# servo_driver_and_imu_device.net
KiCad netlist of a schematic drawn in Altium Designer
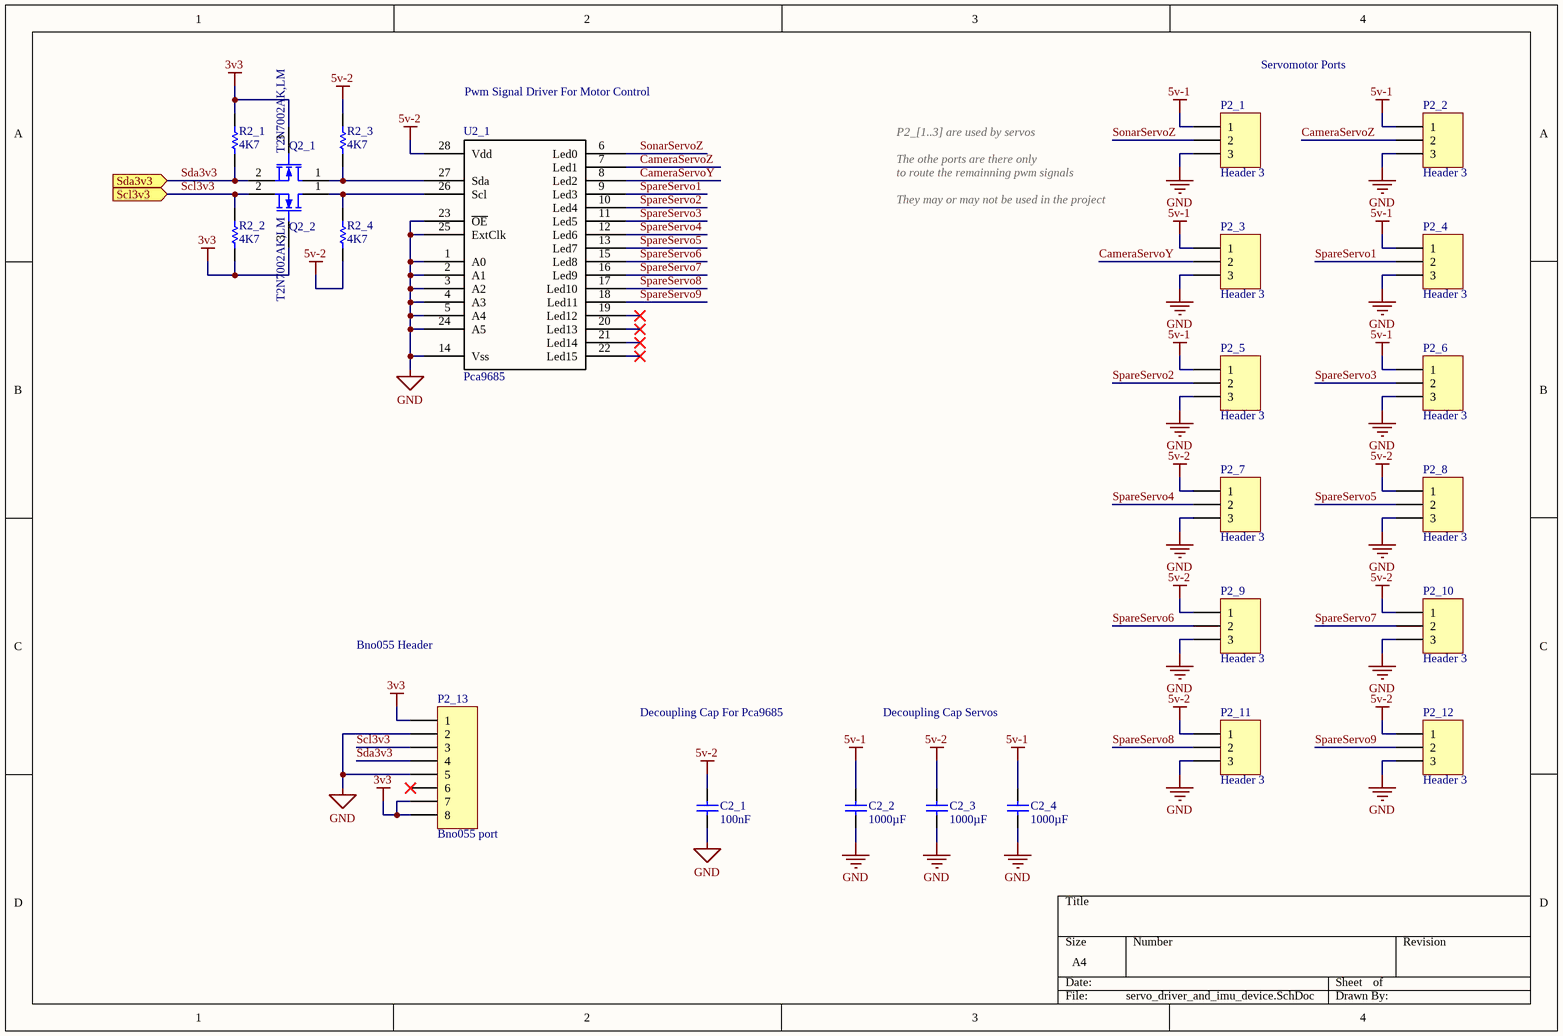
[diagram p0: servo_driver_and_imu_device.SchDoc]

(export (version "E")
  (design (tool "Eeschema 10.0.6"))
  (components
    (comp (ref "C2_1")
      (value "100nF")
      (footprint "C1206")
      (description "Capacitor")
      (fields (field (name "Comment") "12063C104MAT2A") (field (name "PUBLISHER") "Altium Limited"))
      (libsource (lib "Miscellaneous Devices") (part "Cap"))
    )
    (comp (ref "C2_2")
      (value "1000µF")
      (footprint "CAP-ELECTRO-KE0")
      (description "Capacitor")
      (fields (field (name "Comment") "EMHS250GRA102MKE0S") (field (name "PUBLISHER") "Altium Limited"))
      (libsource (lib "Miscellaneous Devices") (part "Cap"))
    )
    (comp (ref "C2_3")
      (value "1000µF")
      (footprint "CAP-ELECTRO-KE0")
      (description "Capacitor")
      (fields (field (name "Comment") "EMHS250GRA102MKE0S") (field (name "PUBLISHER") "Altium Limited"))
      (libsource (lib "Miscellaneous Devices") (part "Cap"))
    )
    (comp (ref "C2_4")
      (value "1000µF")
      (footprint "CAP-ELECTRO-KE0")
      (description "Capacitor")
      (fields (field (name "Comment") "EMHS250GRA102MKE0S") (field (name "PUBLISHER") "Altium Limited"))
      (libsource (lib "Miscellaneous Devices") (part "Cap"))
    )
    (comp (ref "P2_1")
      (value "Header 3")
      (footprint "HDR1X3-42")
      (description "Header, 3-Pin")
      (fields (field (name "PUBLISHER") "Altium Limited"))
      (libsource (lib "Miscellaneous Connectors") (part "Header 3"))
    )
    (comp (ref "P2_2")
      (value "Header 3")
      (footprint "HDR1X3-42")
      (description "Header, 3-Pin")
      (fields (field (name "PUBLISHER") "Altium Limited"))
      (libsource (lib "Miscellaneous Connectors") (part "Header 3"))
    )
    (comp (ref "P2_3")
      (value "Header 3")
      (footprint "HDR1X3-42")
      (description "Header, 3-Pin")
      (fields (field (name "PUBLISHER") "Altium Limited"))
      (libsource (lib "Miscellaneous Connectors") (part "Header 3"))
    )
    (comp (ref "P2_4")
      (value "Header 3")
      (footprint "HDR1X3-42")
      (description "Header, 3-Pin")
      (fields (field (name "PUBLISHER") "Altium Limited"))
      (libsource (lib "Miscellaneous Connectors") (part "Header 3"))
    )
    (comp (ref "P2_5")
      (value "Header 3")
      (footprint "HDR1X3-42")
      (description "Header, 3-Pin")
      (fields (field (name "PUBLISHER") "Altium Limited"))
      (libsource (lib "Miscellaneous Connectors") (part "Header 3"))
    )
    (comp (ref "P2_6")
      (value "Header 3")
      (footprint "HDR1X3-42")
      (description "Header, 3-Pin")
      (fields (field (name "PUBLISHER") "Altium Limited"))
      (libsource (lib "Miscellaneous Connectors") (part "Header 3"))
    )
    (comp (ref "P2_7")
      (value "Header 3")
      (footprint "HDR1X3-42")
      (description "Header, 3-Pin")
      (fields (field (name "PUBLISHER") "Altium Limited"))
      (libsource (lib "Miscellaneous Connectors") (part "Header 3"))
    )
    (comp (ref "P2_8")
      (value "Header 3")
      (footprint "HDR1X3-42")
      (description "Header, 3-Pin")
      (fields (field (name "PUBLISHER") "Altium Limited"))
      (libsource (lib "Miscellaneous Connectors") (part "Header 3"))
    )
    (comp (ref "P2_9")
      (value "Header 3")
      (footprint "HDR1X3-42")
      (description "Header, 3-Pin")
      (fields (field (name "PUBLISHER") "Altium Limited"))
      (libsource (lib "Miscellaneous Connectors") (part "Header 3"))
    )
    (comp (ref "P2_10")
      (value "Header 3")
      (footprint "HDR1X3-42")
      (description "Header, 3-Pin")
      (fields (field (name "PUBLISHER") "Altium Limited"))
      (libsource (lib "Miscellaneous Connectors") (part "Header 3"))
    )
    (comp (ref "P2_11")
      (value "Header 3")
      (footprint "HDR1X3-42")
      (description "Header, 3-Pin")
      (fields (field (name "PUBLISHER") "Altium Limited"))
      (libsource (lib "Miscellaneous Connectors") (part "Header 3"))
    )
    (comp (ref "P2_12")
      (value "Header 3")
      (footprint "HDR1X3-42")
      (description "Header, 3-Pin")
      (fields (field (name "PUBLISHER") "Altium Limited"))
      (libsource (lib "Miscellaneous Connectors") (part "Header 3"))
    )
    (comp (ref "P2_13")
      (value "Bno055 port")
      (footprint "HDR1X8-42")
      (description "Header, 8-Pin")
      (fields (field (name "PUBLISHER") "Altium Limited"))
      (libsource (lib "Miscellaneous Connectors") (part "Header 8"))
    )
    (comp (ref "Q2_1")
      (value "T2N7002AK,LM")
      (footprint "SOT23_L")
      (description "N-Channel MOSFET")
      (fields (field (name "PUBLISHER") "Altium Limited"))
      (libsource (lib "Miscellaneous Devices") (part "MOSFET-N"))
    )
    (comp (ref "Q2_2")
      (value "T2N7002AK,LM")
      (footprint "SOT23_L")
      (description "N-Channel MOSFET")
      (fields (field (name "PUBLISHER") "Altium Limited"))
      (libsource (lib "Miscellaneous Devices") (part "MOSFET-N"))
    )
    (comp (ref "R2_1")
      (value "4K7")
      (footprint "C1206")
      (description "Resistor")
      (fields (field (name "Comment") "Res1") (field (name "PUBLISHER") "Altium Limited"))
      (libsource (lib "Miscellaneous Devices") (part "Res1"))
    )
    (comp (ref "R2_2")
      (value "4K7")
      (footprint "C1206")
      (description "Resistor")
      (fields (field (name "Comment") "Res1") (field (name "PUBLISHER") "Altium Limited"))
      (libsource (lib "Miscellaneous Devices") (part "Res1"))
    )
    (comp (ref "R2_3")
      (value "4K7")
      (footprint "C1206")
      (description "Resistor")
      (fields (field (name "Comment") "Res1") (field (name "PUBLISHER") "Altium Limited"))
      (libsource (lib "Miscellaneous Devices") (part "Res1"))
    )
    (comp (ref "R2_4")
      (value "4K7")
      (footprint "C1206")
      (description "Resistor")
      (fields (field (name "Comment") "Res1") (field (name "PUBLISHER") "Altium Limited"))
      (libsource (lib "Miscellaneous Devices") (part "Res1"))
    )
    (comp (ref "U2_1")
      (value "Pca9685")
      (footprint "SOP65P640X110-28N")
      (description "Serial pwm led driver")
      (libsource (lib "projet 6e session") (part "Pca9685"))
    )
  )
  (nets
    (net (code "1") (name "/CameraServoY") (class "Default")
      (node (ref "P2_3") (pin "2") (pinfunction "2_2") (pintype "passive"))
      (node (ref "U2_1") (pin "8") (pinfunction "Led2_8") (pintype "passive"))
    )
    (net (code "2") (name "/CameraServoZ") (class "Default")
      (node (ref "P2_2") (pin "2") (pinfunction "2_2") (pintype "passive"))
      (node (ref "U2_1") (pin "7") (pinfunction "Led1_7") (pintype "passive"))
    )
    (net (code "3") (name "/Scl3v3") (class "Default")
      (node (ref "P2_13") (pin "3") (pinfunction "3_3") (pintype "passive"))
      (node (ref "Q2_2") (pin "2") (pinfunction "S_2") (pintype "passive"))
      (node (ref "R2_2") (pin "1") (pinfunction "1_1") (pintype "passive"))
    )
    (net (code "4") (name "/Sda3v3") (class "Default")
      (node (ref "P2_13") (pin "4") (pinfunction "4_4") (pintype "passive"))
      (node (ref "Q2_1") (pin "2") (pinfunction "S_2") (pintype "passive"))
      (node (ref "R2_1") (pin "2") (pinfunction "2_2") (pintype "passive"))
    )
    (net (code "5") (name "/SonarServoZ") (class "Default")
      (node (ref "P2_1") (pin "2") (pinfunction "2_2") (pintype "passive"))
      (node (ref "U2_1") (pin "6") (pinfunction "Led0_6") (pintype "passive"))
    )
    (net (code "6") (name "/SpareServo1") (class "Default")
      (node (ref "P2_4") (pin "2") (pinfunction "2_2") (pintype "passive"))
      (node (ref "U2_1") (pin "9") (pinfunction "Led3_9") (pintype "passive"))
    )
    (net (code "7") (name "/SpareServo2") (class "Default")
      (node (ref "P2_5") (pin "2") (pinfunction "2_2") (pintype "passive"))
      (node (ref "U2_1") (pin "10") (pinfunction "Led4_10") (pintype "passive"))
    )
    (net (code "8") (name "/SpareServo3") (class "Default")
      (node (ref "P2_6") (pin "2") (pinfunction "2_2") (pintype "passive"))
      (node (ref "U2_1") (pin "11") (pinfunction "Led5_11") (pintype "passive"))
    )
    (net (code "9") (name "/SpareServo4") (class "Default")
      (node (ref "P2_7") (pin "2") (pinfunction "2_2") (pintype "passive"))
      (node (ref "U2_1") (pin "12") (pinfunction "Led6_12") (pintype "passive"))
    )
    (net (code "10") (name "/SpareServo5") (class "Default")
      (node (ref "P2_8") (pin "2") (pinfunction "2_2") (pintype "passive"))
      (node (ref "U2_1") (pin "13") (pinfunction "Led7_13") (pintype "passive"))
    )
    (net (code "11") (name "/SpareServo6") (class "Default")
      (node (ref "P2_9") (pin "2") (pinfunction "2_2") (pintype "passive"))
      (node (ref "U2_1") (pin "15") (pinfunction "Led8_15") (pintype "passive"))
    )
    (net (code "12") (name "/SpareServo7") (class "Default")
      (node (ref "P2_10") (pin "2") (pinfunction "2_2") (pintype "passive"))
      (node (ref "U2_1") (pin "16") (pinfunction "Led9_16") (pintype "passive"))
    )
    (net (code "13") (name "/SpareServo8") (class "Default")
      (node (ref "P2_11") (pin "2") (pinfunction "2_2") (pintype "passive"))
      (node (ref "U2_1") (pin "17") (pinfunction "Led10_17") (pintype "passive"))
    )
    (net (code "14") (name "/SpareServo9") (class "Default")
      (node (ref "P2_12") (pin "2") (pinfunction "2_2") (pintype "passive"))
      (node (ref "U2_1") (pin "18") (pinfunction "Led11_18") (pintype "passive"))
    )
    (net (code "15") (name "3v3") (class "Default")
      (node (ref "P2_13") (pin "1") (pinfunction "1_1") (pintype "passive"))
      (node (ref "P2_13") (pin "7") (pinfunction "7_7") (pintype "passive"))
      (node (ref "P2_13") (pin "8") (pinfunction "8_8") (pintype "passive"))
      (node (ref "Q2_1") (pin "3") (pinfunction "G_3") (pintype "passive"))
      (node (ref "Q2_2") (pin "3") (pinfunction "G_3") (pintype "passive"))
      (node (ref "R2_1") (pin "1") (pinfunction "1_1") (pintype "passive"))
      (node (ref "R2_2") (pin "2") (pinfunction "2_2") (pintype "passive"))
    )
    (net (code "16") (name "5v-1") (class "Default")
      (node (ref "C2_2") (pin "1") (pinfunction "1_1") (pintype "passive"))
      (node (ref "C2_4") (pin "1") (pinfunction "1_1") (pintype "passive"))
      (node (ref "P2_1") (pin "1") (pinfunction "1_1") (pintype "passive"))
      (node (ref "P2_2") (pin "1") (pinfunction "1_1") (pintype "passive"))
      (node (ref "P2_3") (pin "1") (pinfunction "1_1") (pintype "passive"))
      (node (ref "P2_4") (pin "1") (pinfunction "1_1") (pintype "passive"))
      (node (ref "P2_5") (pin "1") (pinfunction "1_1") (pintype "passive"))
      (node (ref "P2_6") (pin "1") (pinfunction "1_1") (pintype "passive"))
    )
    (net (code "17") (name "5v-2") (class "Default")
      (node (ref "C2_1") (pin "1") (pinfunction "1_1") (pintype "passive"))
      (node (ref "C2_3") (pin "1") (pinfunction "1_1") (pintype "passive"))
      (node (ref "P2_10") (pin "1") (pinfunction "1_1") (pintype "passive"))
      (node (ref "P2_11") (pin "1") (pinfunction "1_1") (pintype "passive"))
      (node (ref "P2_12") (pin "1") (pinfunction "1_1") (pintype "passive"))
      (node (ref "P2_7") (pin "1") (pinfunction "1_1") (pintype "passive"))
      (node (ref "P2_8") (pin "1") (pinfunction "1_1") (pintype "passive"))
      (node (ref "P2_9") (pin "1") (pinfunction "1_1") (pintype "passive"))
      (node (ref "R2_3") (pin "1") (pinfunction "1_1") (pintype "passive"))
      (node (ref "R2_4") (pin "2") (pinfunction "2_2") (pintype "passive"))
      (node (ref "U2_1") (pin "28") (pinfunction "Vdd_28") (pintype "passive"))
    )
    (net (code "18") (name "GND") (class "Default")
      (node (ref "C2_1") (pin "2") (pinfunction "2_2") (pintype "passive"))
      (node (ref "C2_2") (pin "2") (pinfunction "2_2") (pintype "passive"))
      (node (ref "C2_3") (pin "2") (pinfunction "2_2") (pintype "passive"))
      (node (ref "C2_4") (pin "2") (pinfunction "2_2") (pintype "passive"))
      (node (ref "P2_1") (pin "3") (pinfunction "3_3") (pintype "passive"))
      (node (ref "P2_10") (pin "3") (pinfunction "3_3") (pintype "passive"))
      (node (ref "P2_11") (pin "3") (pinfunction "3_3") (pintype "passive"))
      (node (ref "P2_12") (pin "3") (pinfunction "3_3") (pintype "passive"))
      (node (ref "P2_13") (pin "2") (pinfunction "2_2") (pintype "passive"))
      (node (ref "P2_13") (pin "5") (pinfunction "5_5") (pintype "passive"))
      (node (ref "P2_2") (pin "3") (pinfunction "3_3") (pintype "passive"))
      (node (ref "P2_3") (pin "3") (pinfunction "3_3") (pintype "passive"))
      (node (ref "P2_4") (pin "3") (pinfunction "3_3") (pintype "passive"))
      (node (ref "P2_5") (pin "3") (pinfunction "3_3") (pintype "passive"))
      (node (ref "P2_6") (pin "3") (pinfunction "3_3") (pintype "passive"))
      (node (ref "P2_7") (pin "3") (pinfunction "3_3") (pintype "passive"))
      (node (ref "P2_8") (pin "3") (pinfunction "3_3") (pintype "passive"))
      (node (ref "P2_9") (pin "3") (pinfunction "3_3") (pintype "passive"))
      (node (ref "U2_1") (pin "1") (pinfunction "A0_1") (pintype "passive"))
      (node (ref "U2_1") (pin "14") (pinfunction "Vss_14") (pintype "passive"))
      (node (ref "U2_1") (pin "2") (pinfunction "A1_2") (pintype "passive"))
      (node (ref "U2_1") (pin "23") (pinfunction "~{OE}_23") (pintype "passive"))
      (node (ref "U2_1") (pin "24") (pinfunction "A5_24") (pintype "passive"))
      (node (ref "U2_1") (pin "25") (pinfunction "ExtClk_25") (pintype "passive"))
      (node (ref "U2_1") (pin "3") (pinfunction "A2_3") (pintype "passive"))
      (node (ref "U2_1") (pin "4") (pinfunction "A3_4") (pintype "passive"))
      (node (ref "U2_1") (pin "5") (pinfunction "A4_5") (pintype "passive"))
    )
    (net (code "19") (name "Net-(Q2_1-D)") (class "Default")
      (node (ref "Q2_1") (pin "1") (pinfunction "D_1") (pintype "passive"))
      (node (ref "R2_3") (pin "2") (pinfunction "2_2") (pintype "passive"))
      (node (ref "U2_1") (pin "27") (pinfunction "Sda_27") (pintype "passive"))
    )
    (net (code "20") (name "Net-(Q2_2-D)") (class "Default")
      (node (ref "Q2_2") (pin "1") (pinfunction "D_1") (pintype "passive"))
      (node (ref "R2_4") (pin "1") (pinfunction "1_1") (pintype "passive"))
      (node (ref "U2_1") (pin "26") (pinfunction "Scl_26") (pintype "passive"))
    )
    (net (code "21") (name "unconnected-(P2_13-Pad6)") (class "Default")
      (node (ref "P2_13") (pin "6") (pinfunction "6_6") (pintype "passive+no_connect"))
    )
    (net (code "22") (name "unconnected-(U2_1-Led12-Pad19)") (class "Default")
      (node (ref "U2_1") (pin "19") (pinfunction "Led12_19") (pintype "passive+no_connect"))
    )
    (net (code "23") (name "unconnected-(U2_1-Led13-Pad20)") (class "Default")
      (node (ref "U2_1") (pin "20") (pinfunction "Led13_20") (pintype "passive+no_connect"))
    )
    (net (code "24") (name "unconnected-(U2_1-Led14-Pad21)") (class "Default")
      (node (ref "U2_1") (pin "21") (pinfunction "Led14_21") (pintype "passive+no_connect"))
    )
    (net (code "25") (name "unconnected-(U2_1-Led15-Pad22)") (class "Default")
      (node (ref "U2_1") (pin "22") (pinfunction "Led15_22") (pintype "passive+no_connect"))
    )
  )
)
